# SAMD21_16X10_schematic.net
KiCad netlist of a schematic drawn in Altium Designer
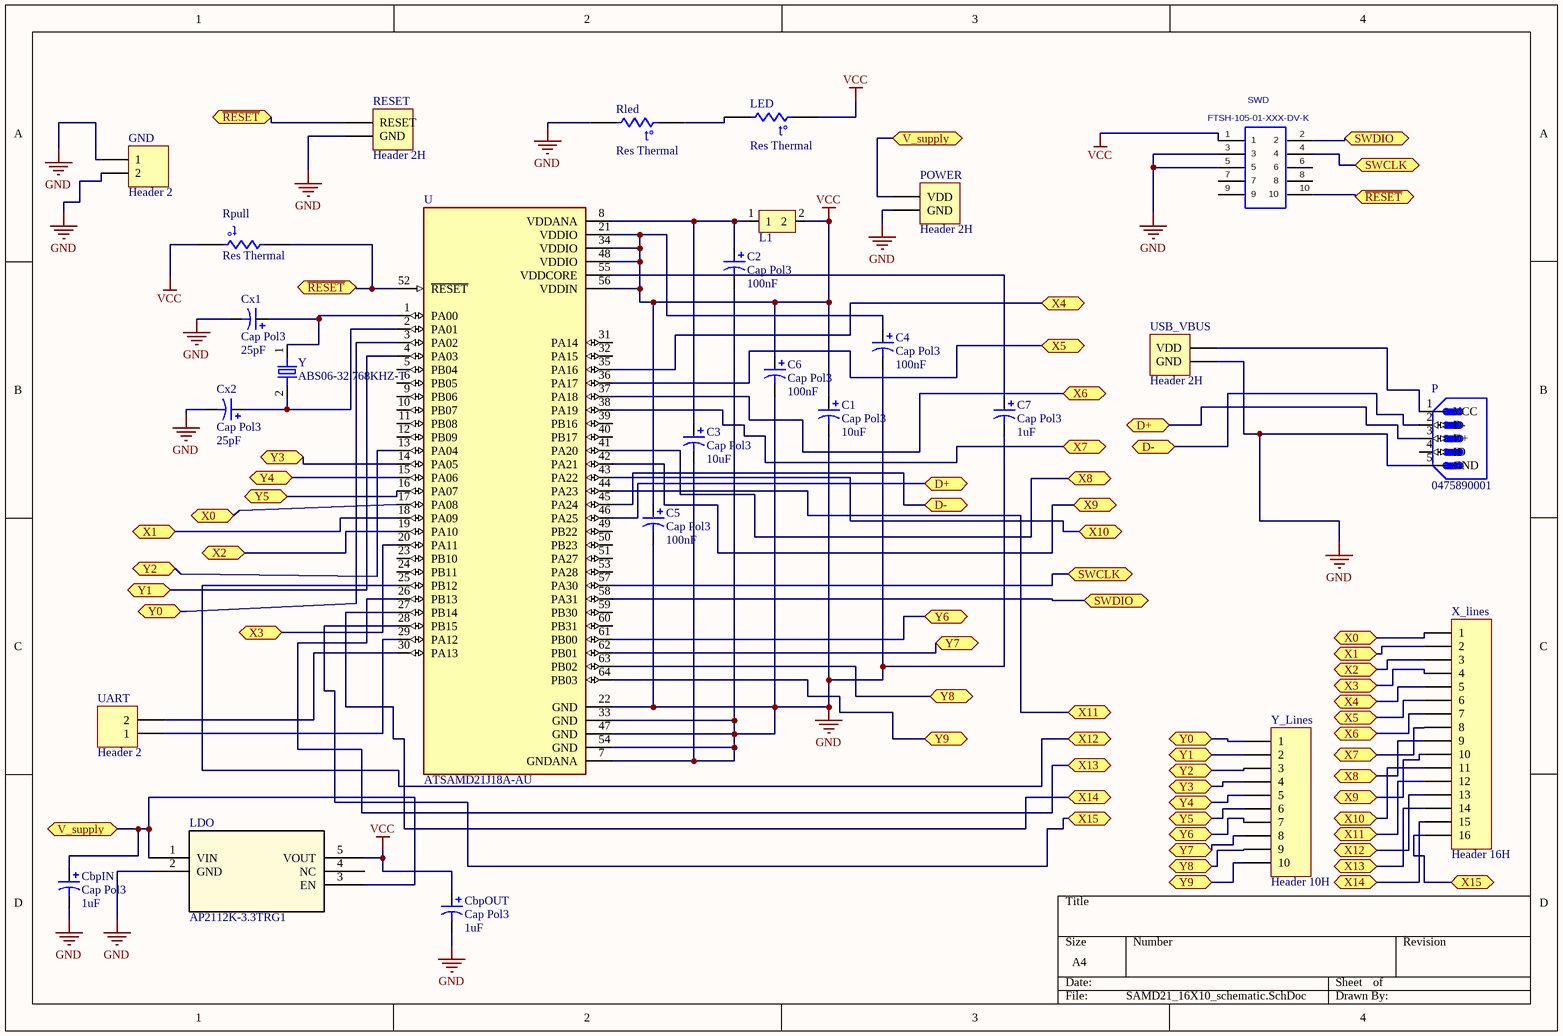
[diagram p0: SAMD21_16X10_schematic.SchDoc]

(export (version "E")
  (design (tool "Eeschema 10.0.6"))
  (components
    (comp (ref "C1")
      (value "Cap Pol3")
      (footprint "C0805")
      (description "Polarized Capacitor (Surface Mount)")
      (fields (field (name "ALTIUM_VALUE") "10uF") (field (name "PUBLISHER") "Altium Limited"))
      (libsource (lib "Miscellaneous Devices") (part "Cap Pol3"))
    )
    (comp (ref "C2")
      (value "Cap Pol3")
      (footprint "C0805")
      (description "Polarized Capacitor (Surface Mount)")
      (fields (field (name "ALTIUM_VALUE") "100nF") (field (name "PUBLISHER") "Altium Limited"))
      (libsource (lib "Miscellaneous Devices") (part "Cap Pol3"))
    )
    (comp (ref "C3")
      (value "Cap Pol3")
      (footprint "C0805")
      (description "Polarized Capacitor (Surface Mount)")
      (fields (field (name "ALTIUM_VALUE") "10uF") (field (name "PUBLISHER") "Altium Limited"))
      (libsource (lib "Miscellaneous Devices") (part "Cap Pol3"))
    )
    (comp (ref "C4")
      (value "Cap Pol3")
      (footprint "C0805")
      (description "Polarized Capacitor (Surface Mount)")
      (fields (field (name "ALTIUM_VALUE") "100nF") (field (name "PUBLISHER") "Altium Limited"))
      (libsource (lib "Miscellaneous Devices") (part "Cap Pol3"))
    )
    (comp (ref "C5")
      (value "Cap Pol3")
      (footprint "C0805")
      (description "Polarized Capacitor (Surface Mount)")
      (fields (field (name "ALTIUM_VALUE") "100nF") (field (name "PUBLISHER") "Altium Limited"))
      (libsource (lib "Miscellaneous Devices") (part "Cap Pol3"))
    )
    (comp (ref "C6")
      (value "Cap Pol3")
      (footprint "C0805")
      (description "Polarized Capacitor (Surface Mount)")
      (fields (field (name "ALTIUM_VALUE") "100nF") (field (name "PUBLISHER") "Altium Limited"))
      (libsource (lib "Miscellaneous Devices") (part "Cap Pol3"))
    )
    (comp (ref "C7")
      (value "Cap Pol3")
      (footprint "C0805")
      (description "Polarized Capacitor (Surface Mount)")
      (fields (field (name "ALTIUM_VALUE") "1uF") (field (name "PUBLISHER") "Altium Limited"))
      (libsource (lib "Miscellaneous Devices") (part "Cap Pol3"))
    )
    (comp (ref "CbpIN")
      (value "Cap Pol3")
      (footprint "C0805")
      (description "Polarized Capacitor (Surface Mount)")
      (fields (field (name "ALTIUM_VALUE") "1uF") (field (name "PUBLISHER") "Altium Limited"))
      (libsource (lib "Miscellaneous Devices") (part "Cap Pol3"))
    )
    (comp (ref "CbpOUT")
      (value "Cap Pol3")
      (footprint "C0805")
      (description "Polarized Capacitor (Surface Mount)")
      (fields (field (name "ALTIUM_VALUE") "1uF") (field (name "PUBLISHER") "Altium Limited"))
      (libsource (lib "Miscellaneous Devices") (part "Cap Pol3"))
    )
    (comp (ref "Cx1")
      (value "Cap Pol3")
      (footprint "C0805")
      (description "Polarized Capacitor (Surface Mount)")
      (fields (field (name "ALTIUM_VALUE") "25pF") (field (name "PUBLISHER") "Altium Limited"))
      (libsource (lib "Miscellaneous Devices") (part "Cap Pol3"))
    )
    (comp (ref "Cx2")
      (value "Cap Pol3")
      (footprint "C0805")
      (description "Polarized Capacitor (Surface Mount)")
      (fields (field (name "ALTIUM_VALUE") "25pF") (field (name "PUBLISHER") "Altium Limited"))
      (libsource (lib "Miscellaneous Devices") (part "Cap Pol3"))
    )
    (comp (ref "GND")
      (value "Header 2")
      (footprint "HDR1X2")
      (description "Header, 2-Pin")
      (fields (field (name "PUBLISHER") "Altium Limited"))
      (libsource (lib "") (part "Header 2_1"))
    )
    (comp (ref "L1")
      (value "SRP4012TA-100M")
      (footprint "Inductor")
      (description "Inductor")
      (libsource (lib "SRP4012TA") (part "SRP4012TA-100M"))
    )
    (comp (ref "LDO")
      (value "AP2112K-3.3TRG1")
      (footprint "SOT_RG1_DIO")
      (description "No Description Available")
      (fields (field (name "COPYRIGHT") "Copyright (C) 2018 Accelerated Designs. All rights reserved"))
      (libsource (lib "2020-09-03_20-14-04") (part "AP2112K-3.3TRG1"))
    )
    (comp (ref "LED")
      (value "Res Thermal")
      (footprint "6-0805_N")
      (description "Thermistor")
      (fields (field (name "PUBLISHER") "Altium Limited"))
      (libsource (lib "Miscellaneous Devices") (part "Res Thermal"))
    )
    (comp (ref "P")
      (value "0475890001")
      (footprint "MOLEX_0475890001")
      (description "USB - micro AB Receptacle Connector 5 Position Surface Mount, Right Angle; Through Hole")
      (fields (field (name "DIGI-KEY_PART_NUMBER") "WM17143CT-ND") (field (name "MF") "Molex"))
      (libsource (lib "0475890001") (part "0475890001"))
    )
    (comp (ref "POWER")
      (value "Header 2H")
      (footprint "HDR1X2H")
      (description "Header, 2-Pin, Right Angle")
      (fields (field (name "PUBLISHER") "Altium Limited"))
      (libsource (lib "Miscellaneous Connectors") (part "Header 2H"))
    )
    (comp (ref "RESET")
      (value "Header 2H")
      (footprint "HDR1X2H")
      (description "Header, 2-Pin, Right Angle")
      (fields (field (name "PUBLISHER") "Altium Limited"))
      (libsource (lib "Miscellaneous Connectors") (part "Header 2H"))
    )
    (comp (ref "Rled")
      (value "Res Thermal")
      (footprint "6-0805_N")
      (description "Thermistor")
      (fields (field (name "PUBLISHER") "Altium Limited"))
      (libsource (lib "Miscellaneous Devices") (part "Res Thermal"))
    )
    (comp (ref "Rpull")
      (value "Res Thermal")
      (footprint "6-0805_N")
      (description "Thermistor")
      (fields (field (name "PUBLISHER") "Altium Limited"))
      (libsource (lib "Miscellaneous Devices") (part "Res Thermal"))
    )
    (comp (ref "SWD")
      (value "FTSH-105-01-XXX-DV-K")
      (footprint "FTSH-105-01-XXX-DV-K")
      (description "TERMINAL STRIP, .050\"(1.27mm) PITCH, 10 PINS, KEYED")
      (fields (field (name "MANUFACTURER") "SAMTEC") (field (name "CREATED") "November 30, 2016 - Wendy Xin"))
      (libsource (lib "FTSH-105-01-XXX-DV-K--Symbol-Altium-44987") (part "FTSH-105-01-XXX-DV-K"))
    )
    (comp (ref "U")
      (value "ATSAMD21J18A-AU")
      (footprint "QFP80P1600X1600X120-64N")
      (description "ARMÂ® CortexÂ®-M0+ SAM D21J Microcontroller IC 32-Bit 48MHz 256KB _256K x 8_ FLASH 64-TQFP _10x10_")
      (fields (field (name "MF") "Microchip"))
      (libsource (lib "ATSAMD21J18A-AU") (part "ATSAMD21J18A-AU"))
    )
    (comp (ref "UART")
      (value "Header 2")
      (footprint "HDR1X2")
      (description "Header, 2-Pin")
      (fields (field (name "PUBLISHER") "Altium Limited"))
      (libsource (lib "Miscellaneous Connectors") (part "Header 2"))
    )
    (comp (ref "USB_VBUS")
      (value "Header 2H")
      (footprint "HDR1X2H")
      (description "Header, 2-Pin, Right Angle")
      (fields (field (name "PUBLISHER") "Altium Limited"))
      (libsource (lib "") (part "Header 2H_1"))
    )
    (comp (ref "X_lines")
      (value "Header 16H")
      (footprint "HDR1X16H")
      (description "Header, 16-Pin, Right Angle")
      (fields (field (name "PUBLISHER") "Altium Limited"))
      (libsource (lib "Miscellaneous Connectors") (part "Header 16H"))
    )
    (comp (ref "Y")
      (value "ABS06-32.768KHZ-T")
      (footprint "XTAL_ABS06-32.768KHZ-T")
      (description "32.768kHz Â±20ppm Crystal 12.5pF 90 kOhms 2-SMD, No Lead")
      (fields (field (name "MF") "Abracon"))
      (libsource (lib "ABS06-32.768KHZ-T") (part "ABS06-32.768KHZ-T"))
    )
    (comp (ref "Y_Lines")
      (value "Header 10H")
      (footprint "HDR1X10H")
      (description "Header, 10-Pin, Right Angle")
      (fields (field (name "PUBLISHER") "Altium Limited"))
      (libsource (lib "Miscellaneous Connectors") (part "Header 10H"))
    )
  )
  (nets
    (net (code "1") (name "/D+") (class "Default")
      (node (ref "P") (pin "3") (pinfunction "D+_3") (pintype "bidirectional"))
      (node (ref "U") (pin "46") (pinfunction "PA25_46") (pintype "bidirectional"))
    )
    (net (code "2") (name "/D-") (class "Default")
      (node (ref "P") (pin "2") (pinfunction "D-_2") (pintype "bidirectional"))
      (node (ref "U") (pin "45") (pinfunction "PA24_45") (pintype "bidirectional"))
    )
    (net (code "3") (name "/SWCLK") (class "Default")
      (node (ref "SWD") (pin "4") (pinfunction "4_4") (pintype "passive"))
      (node (ref "U") (pin "57") (pinfunction "PA30_57") (pintype "bidirectional"))
    )
    (net (code "4") (name "/SWDIO") (class "Default")
      (node (ref "SWD") (pin "2") (pinfunction "2_2") (pintype "passive"))
      (node (ref "U") (pin "58") (pinfunction "PA31_58") (pintype "bidirectional"))
    )
    (net (code "5") (name "/V_supply") (class "Default")
      (node (ref "CbpIN") (pin "1") (pinfunction "1_1") (pintype "passive"))
      (node (ref "LDO") (pin "1") (pinfunction "VIN_1") (pintype "passive"))
      (node (ref "LDO") (pin "3") (pinfunction "EN_3") (pintype "passive"))
      (node (ref "POWER") (pin "1") (pinfunction "RESET_1") (pintype "passive"))
    )
    (net (code "6") (name "/X0") (class "Default")
      (node (ref "U") (pin "17") (pinfunction "PA08_17") (pintype "bidirectional"))
      (node (ref "X_lines") (pin "1") (pinfunction "1_1") (pintype "passive"))
    )
    (net (code "7") (name "/X1") (class "Default")
      (node (ref "U") (pin "18") (pinfunction "PA09_18") (pintype "bidirectional"))
      (node (ref "X_lines") (pin "2") (pinfunction "2_2") (pintype "passive"))
    )
    (net (code "8") (name "/X2") (class "Default")
      (node (ref "U") (pin "19") (pinfunction "PA10_19") (pintype "bidirectional"))
      (node (ref "X_lines") (pin "3") (pinfunction "3_3") (pintype "passive"))
    )
    (net (code "9") (name "/X3") (class "Default")
      (node (ref "U") (pin "20") (pinfunction "PA11_20") (pintype "bidirectional"))
      (node (ref "X_lines") (pin "4") (pinfunction "4_4") (pintype "passive"))
    )
    (net (code "10") (name "/X4") (class "Default")
      (node (ref "U") (pin "35") (pinfunction "PA16_35") (pintype "bidirectional"))
      (node (ref "X_lines") (pin "5") (pinfunction "5_5") (pintype "passive"))
    )
    (net (code "11") (name "/X5") (class "Default")
      (node (ref "U") (pin "36") (pinfunction "PA17_36") (pintype "bidirectional"))
      (node (ref "X_lines") (pin "6") (pinfunction "6_6") (pintype "passive"))
    )
    (net (code "12") (name "/X6") (class "Default")
      (node (ref "U") (pin "37") (pinfunction "PA18_37") (pintype "bidirectional"))
      (node (ref "X_lines") (pin "7") (pinfunction "7_7") (pintype "passive"))
    )
    (net (code "13") (name "/X7") (class "Default")
      (node (ref "U") (pin "38") (pinfunction "PA19_38") (pintype "bidirectional"))
      (node (ref "X_lines") (pin "8") (pinfunction "8_8") (pintype "passive"))
    )
    (net (code "14") (name "/X8") (class "Default")
      (node (ref "U") (pin "41") (pinfunction "PA20_41") (pintype "bidirectional"))
      (node (ref "X_lines") (pin "9") (pinfunction "9_9") (pintype "passive"))
    )
    (net (code "15") (name "/X9") (class "Default")
      (node (ref "U") (pin "42") (pinfunction "PA21_42") (pintype "bidirectional"))
      (node (ref "X_lines") (pin "10") (pinfunction "10_10") (pintype "passive"))
    )
    (net (code "16") (name "/X10") (class "Default")
      (node (ref "U") (pin "43") (pinfunction "PA22_43") (pintype "bidirectional"))
      (node (ref "X_lines") (pin "11") (pinfunction "11_11") (pintype "passive"))
    )
    (net (code "17") (name "/X11") (class "Default")
      (node (ref "U") (pin "44") (pinfunction "PA23_44") (pintype "bidirectional"))
      (node (ref "X_lines") (pin "12") (pinfunction "12_12") (pintype "passive"))
    )
    (net (code "18") (name "/X12") (class "Default")
      (node (ref "U") (pin "25") (pinfunction "PB12_25") (pintype "bidirectional"))
      (node (ref "X_lines") (pin "13") (pinfunction "13_13") (pintype "passive"))
    )
    (net (code "19") (name "/X13") (class "Default")
      (node (ref "U") (pin "26") (pinfunction "PB13_26") (pintype "bidirectional"))
      (node (ref "X_lines") (pin "14") (pinfunction "14_14") (pintype "passive"))
    )
    (net (code "20") (name "/X14") (class "Default")
      (node (ref "U") (pin "27") (pinfunction "PB14_27") (pintype "bidirectional"))
      (node (ref "X_lines") (pin "15") (pinfunction "15_15") (pintype "passive"))
    )
    (net (code "21") (name "/X15") (class "Default")
      (node (ref "U") (pin "28") (pinfunction "PB15_28") (pintype "bidirectional"))
      (node (ref "X_lines") (pin "16") (pinfunction "16_16") (pintype "passive"))
    )
    (net (code "22") (name "/Y0") (class "Default")
      (node (ref "U") (pin "3") (pinfunction "PA02_3") (pintype "bidirectional"))
      (node (ref "Y_Lines") (pin "1") (pinfunction "1_1") (pintype "passive"))
    )
    (net (code "23") (name "/Y1") (class "Default")
      (node (ref "U") (pin "4") (pinfunction "PA03_4") (pintype "bidirectional"))
      (node (ref "Y_Lines") (pin "2") (pinfunction "2_2") (pintype "passive"))
    )
    (net (code "24") (name "/Y2") (class "Default")
      (node (ref "U") (pin "13") (pinfunction "PA04_13") (pintype "bidirectional"))
      (node (ref "Y_Lines") (pin "3") (pinfunction "3_3") (pintype "passive"))
    )
    (net (code "25") (name "/Y3") (class "Default")
      (node (ref "U") (pin "14") (pinfunction "PA05_14") (pintype "bidirectional"))
      (node (ref "Y_Lines") (pin "4") (pinfunction "4_4") (pintype "passive"))
    )
    (net (code "26") (name "/Y4") (class "Default")
      (node (ref "U") (pin "15") (pinfunction "PA06_15") (pintype "bidirectional"))
      (node (ref "Y_Lines") (pin "5") (pinfunction "5_5") (pintype "passive"))
    )
    (net (code "27") (name "/Y5") (class "Default")
      (node (ref "U") (pin "16") (pinfunction "PA07_16") (pintype "bidirectional"))
      (node (ref "Y_Lines") (pin "6") (pinfunction "6_6") (pintype "passive"))
    )
    (net (code "28") (name "/Y6") (class "Default")
      (node (ref "U") (pin "61") (pinfunction "PB00_61") (pintype "bidirectional"))
      (node (ref "Y_Lines") (pin "7") (pinfunction "7_7") (pintype "passive"))
    )
    (net (code "29") (name "/Y7") (class "Default")
      (node (ref "U") (pin "62") (pinfunction "PB01_62") (pintype "bidirectional"))
      (node (ref "Y_Lines") (pin "8") (pinfunction "8_8") (pintype "passive"))
    )
    (net (code "30") (name "/Y8") (class "Default")
      (node (ref "U") (pin "63") (pinfunction "PB02_63") (pintype "bidirectional"))
      (node (ref "Y_Lines") (pin "9") (pinfunction "9_9") (pintype "passive"))
    )
    (net (code "31") (name "/Y9") (class "Default")
      (node (ref "U") (pin "64") (pinfunction "PB03_64") (pintype "bidirectional"))
      (node (ref "Y_Lines") (pin "10") (pinfunction "10_10") (pintype "passive"))
    )
    (net (code "32") (name "/~{RESET}") (class "Default")
      (node (ref "RESET") (pin "1") (pinfunction "RESET_1") (pintype "passive"))
      (node (ref "Rpull") (pin "2") (pinfunction "2_2") (pintype "passive"))
      (node (ref "SWD") (pin "10") (pinfunction "10_10") (pintype "passive"))
      (node (ref "U") (pin "52") (pinfunction "~{RESET}_52") (pintype "input"))
    )
    (net (code "33") (name "GND") (class "Default")
      (node (ref "C1") (pin "2") (pinfunction "2_2") (pintype "passive"))
      (node (ref "C2") (pin "2") (pinfunction "2_2") (pintype "passive"))
      (node (ref "C3") (pin "2") (pinfunction "2_2") (pintype "passive"))
      (node (ref "C4") (pin "2") (pinfunction "2_2") (pintype "passive"))
      (node (ref "C5") (pin "2") (pinfunction "2_2") (pintype "passive"))
      (node (ref "C6") (pin "2") (pinfunction "2_2") (pintype "passive"))
      (node (ref "C7") (pin "2") (pinfunction "2_2") (pintype "passive"))
      (node (ref "CbpIN") (pin "2") (pinfunction "2_2") (pintype "passive"))
      (node (ref "CbpOUT") (pin "2") (pinfunction "2_2") (pintype "passive"))
      (node (ref "Cx1") (pin "2") (pinfunction "2_2") (pintype "passive"))
      (node (ref "Cx2") (pin "2") (pinfunction "2_2") (pintype "passive"))
      (node (ref "GND") (pin "1") (pinfunction "1_1") (pintype "passive"))
      (node (ref "GND") (pin "2") (pinfunction "2_2") (pintype "passive"))
      (node (ref "LDO") (pin "2") (pinfunction "GND_2") (pintype "passive"))
      (node (ref "P") (pin "5") (pinfunction "GND_5") (pintype "power_in"))
      (node (ref "POWER") (pin "2") (pinfunction "GND_2") (pintype "passive"))
      (node (ref "RESET") (pin "2") (pinfunction "GND_2") (pintype "passive"))
      (node (ref "Rled") (pin "2") (pinfunction "2_2") (pintype "passive"))
      (node (ref "SWD") (pin "3") (pinfunction "3_3") (pintype "passive"))
      (node (ref "SWD") (pin "5") (pinfunction "5_5") (pintype "passive"))
      (node (ref "U") (pin "22") (pinfunction "GND_22") (pintype "power_in"))
      (node (ref "U") (pin "33") (pinfunction "GND_33") (pintype "power_in"))
      (node (ref "U") (pin "47") (pinfunction "GND_47") (pintype "power_in"))
      (node (ref "U") (pin "54") (pinfunction "GND_54") (pintype "power_in"))
      (node (ref "U") (pin "7") (pinfunction "GNDANA_7") (pintype "power_in"))
      (node (ref "USB_VBUS") (pin "1") (pinfunction "GND_1") (pintype "passive"))
    )
    (net (code "34") (name "Net-(LED-Pad2)") (class "Default")
      (node (ref "LED") (pin "2") (pinfunction "2_2") (pintype "passive"))
      (node (ref "Rled") (pin "1") (pinfunction "1_1") (pintype "passive"))
    )
    (net (code "35") (name "Net-(P-VCC)") (class "Default")
      (node (ref "P") (pin "1") (pinfunction "VCC_1") (pintype "power_in"))
      (node (ref "USB_VBUS") (pin "2") (pinfunction "VDD_2") (pintype "passive"))
    )
    (net (code "36") (name "Net-(U-PA00)") (class "Default")
      (node (ref "Cx1") (pin "1") (pinfunction "1_1") (pintype "passive"))
      (node (ref "U") (pin "1") (pinfunction "PA00_1") (pintype "bidirectional"))
      (node (ref "Y") (pin "1") (pinfunction "1_1") (pintype "passive"))
    )
    (net (code "37") (name "Net-(U-PA01)") (class "Default")
      (node (ref "Cx2") (pin "1") (pinfunction "1_1") (pintype "passive"))
      (node (ref "U") (pin "2") (pinfunction "PA01_2") (pintype "bidirectional"))
      (node (ref "Y") (pin "2") (pinfunction "2_2") (pintype "passive"))
    )
    (net (code "38") (name "Net-(U-PA12)") (class "Default")
      (node (ref "U") (pin "29") (pinfunction "PA12_29") (pintype "bidirectional"))
      (node (ref "UART") (pin "1") (pinfunction "1_1") (pintype "passive"))
    )
    (net (code "39") (name "Net-(U-PA13)") (class "Default")
      (node (ref "U") (pin "30") (pinfunction "PA13_30") (pintype "bidirectional"))
      (node (ref "UART") (pin "2") (pinfunction "2_2") (pintype "passive"))
    )
    (net (code "40") (name "Net-(U-VDDANA)") (class "Default")
      (node (ref "C2") (pin "1") (pinfunction "1_1") (pintype "passive"))
      (node (ref "C3") (pin "1") (pinfunction "1_1") (pintype "passive"))
      (node (ref "L1") (pin "1") (pinfunction "1_1") (pintype "passive"))
      (node (ref "U") (pin "8") (pinfunction "VDDANA_8") (pintype "power_in"))
    )
    (net (code "41") (name "Net-(U-VDDCORE)") (class "Default")
      (node (ref "C7") (pin "1") (pinfunction "1_1") (pintype "passive"))
      (node (ref "U") (pin "55") (pinfunction "VDDCORE_55") (pintype "power_in"))
    )
    (net (code "42") (name "VCC") (class "Default")
      (node (ref "C1") (pin "1") (pinfunction "1_1") (pintype "passive"))
      (node (ref "C4") (pin "1") (pinfunction "1_1") (pintype "passive"))
      (node (ref "C5") (pin "1") (pinfunction "1_1") (pintype "passive"))
      (node (ref "C6") (pin "1") (pinfunction "1_1") (pintype "passive"))
      (node (ref "CbpOUT") (pin "1") (pinfunction "1_1") (pintype "passive"))
      (node (ref "L1") (pin "2") (pinfunction "2_2") (pintype "passive"))
      (node (ref "LDO") (pin "5") (pinfunction "VOUT_5") (pintype "passive"))
      (node (ref "LED") (pin "1") (pinfunction "1_1") (pintype "passive"))
      (node (ref "Rpull") (pin "1") (pinfunction "1_1") (pintype "passive"))
      (node (ref "SWD") (pin "1") (pinfunction "1_1") (pintype "passive"))
      (node (ref "U") (pin "21") (pinfunction "VDDIO_21") (pintype "power_in"))
      (node (ref "U") (pin "34") (pinfunction "VDDIO_34") (pintype "power_in"))
      (node (ref "U") (pin "48") (pinfunction "VDDIO_48") (pintype "power_in"))
      (node (ref "U") (pin "56") (pinfunction "VDDIN_56") (pintype "power_in"))
    )
    (net (code "43") (name "unconnected-(LDO-NC-Pad4)") (class "Default")
      (node (ref "LDO") (pin "4") (pinfunction "NC_4") (pintype "passive"))
    )
    (net (code "44") (name "unconnected-(P-ID-Pad4)") (class "Default")
      (node (ref "P") (pin "4") (pinfunction "ID_4") (pintype "bidirectional"))
    )
    (net (code "45") (name "unconnected-(SWD-Pad6)") (class "Default")
      (node (ref "SWD") (pin "6") (pinfunction "6_6") (pintype "passive"))
    )
    (net (code "46") (name "unconnected-(SWD-Pad7)") (class "Default")
      (node (ref "SWD") (pin "7") (pinfunction "7_7") (pintype "passive"))
    )
    (net (code "47") (name "unconnected-(SWD-Pad8)") (class "Default")
      (node (ref "SWD") (pin "8") (pinfunction "8_8") (pintype "passive"))
    )
    (net (code "48") (name "unconnected-(SWD-Pad9)") (class "Default")
      (node (ref "SWD") (pin "9") (pinfunction "9_9") (pintype "passive"))
    )
    (net (code "49") (name "unconnected-(U-PA14-Pad31)") (class "Default")
      (node (ref "U") (pin "31") (pinfunction "PA14_31") (pintype "bidirectional"))
    )
    (net (code "50") (name "unconnected-(U-PA15-Pad32)") (class "Default")
      (node (ref "U") (pin "32") (pinfunction "PA15_32") (pintype "bidirectional"))
    )
    (net (code "51") (name "unconnected-(U-PA27-Pad51)") (class "Default")
      (node (ref "U") (pin "51") (pinfunction "PA27_51") (pintype "bidirectional"))
    )
    (net (code "52") (name "unconnected-(U-PA28-Pad53)") (class "Default")
      (node (ref "U") (pin "53") (pinfunction "PA28_53") (pintype "bidirectional"))
    )
    (net (code "53") (name "unconnected-(U-PB04-Pad5)") (class "Default")
      (node (ref "U") (pin "5") (pinfunction "PB04_5") (pintype "bidirectional"))
    )
    (net (code "54") (name "unconnected-(U-PB05-Pad6)") (class "Default")
      (node (ref "U") (pin "6") (pinfunction "PB05_6") (pintype "bidirectional"))
    )
    (net (code "55") (name "unconnected-(U-PB06-Pad9)") (class "Default")
      (node (ref "U") (pin "9") (pinfunction "PB06_9") (pintype "bidirectional"))
    )
    (net (code "56") (name "unconnected-(U-PB07-Pad10)") (class "Default")
      (node (ref "U") (pin "10") (pinfunction "PB07_10") (pintype "bidirectional"))
    )
    (net (code "57") (name "unconnected-(U-PB08-Pad11)") (class "Default")
      (node (ref "U") (pin "11") (pinfunction "PB08_11") (pintype "bidirectional"))
    )
    (net (code "58") (name "unconnected-(U-PB09-Pad12)") (class "Default")
      (node (ref "U") (pin "12") (pinfunction "PB09_12") (pintype "bidirectional"))
    )
    (net (code "59") (name "unconnected-(U-PB10-Pad23)") (class "Default")
      (node (ref "U") (pin "23") (pinfunction "PB10_23") (pintype "bidirectional"))
    )
    (net (code "60") (name "unconnected-(U-PB11-Pad24)") (class "Default")
      (node (ref "U") (pin "24") (pinfunction "PB11_24") (pintype "bidirectional"))
    )
    (net (code "61") (name "unconnected-(U-PB16-Pad39)") (class "Default")
      (node (ref "U") (pin "39") (pinfunction "PB16_39") (pintype "bidirectional"))
    )
    (net (code "62") (name "unconnected-(U-PB17-Pad40)") (class "Default")
      (node (ref "U") (pin "40") (pinfunction "PB17_40") (pintype "bidirectional"))
    )
    (net (code "63") (name "unconnected-(U-PB22-Pad49)") (class "Default")
      (node (ref "U") (pin "49") (pinfunction "PB22_49") (pintype "bidirectional"))
    )
    (net (code "64") (name "unconnected-(U-PB23-Pad50)") (class "Default")
      (node (ref "U") (pin "50") (pinfunction "PB23_50") (pintype "bidirectional"))
    )
    (net (code "65") (name "unconnected-(U-PB30-Pad59)") (class "Default")
      (node (ref "U") (pin "59") (pinfunction "PB30_59") (pintype "bidirectional"))
    )
    (net (code "66") (name "unconnected-(U-PB31-Pad60)") (class "Default")
      (node (ref "U") (pin "60") (pinfunction "PB31_60") (pintype "bidirectional"))
    )
  )
)
